# SCH_Media-Remote_2024-07-10.net
KiCad netlist of a schematic drawn in EasyEDA
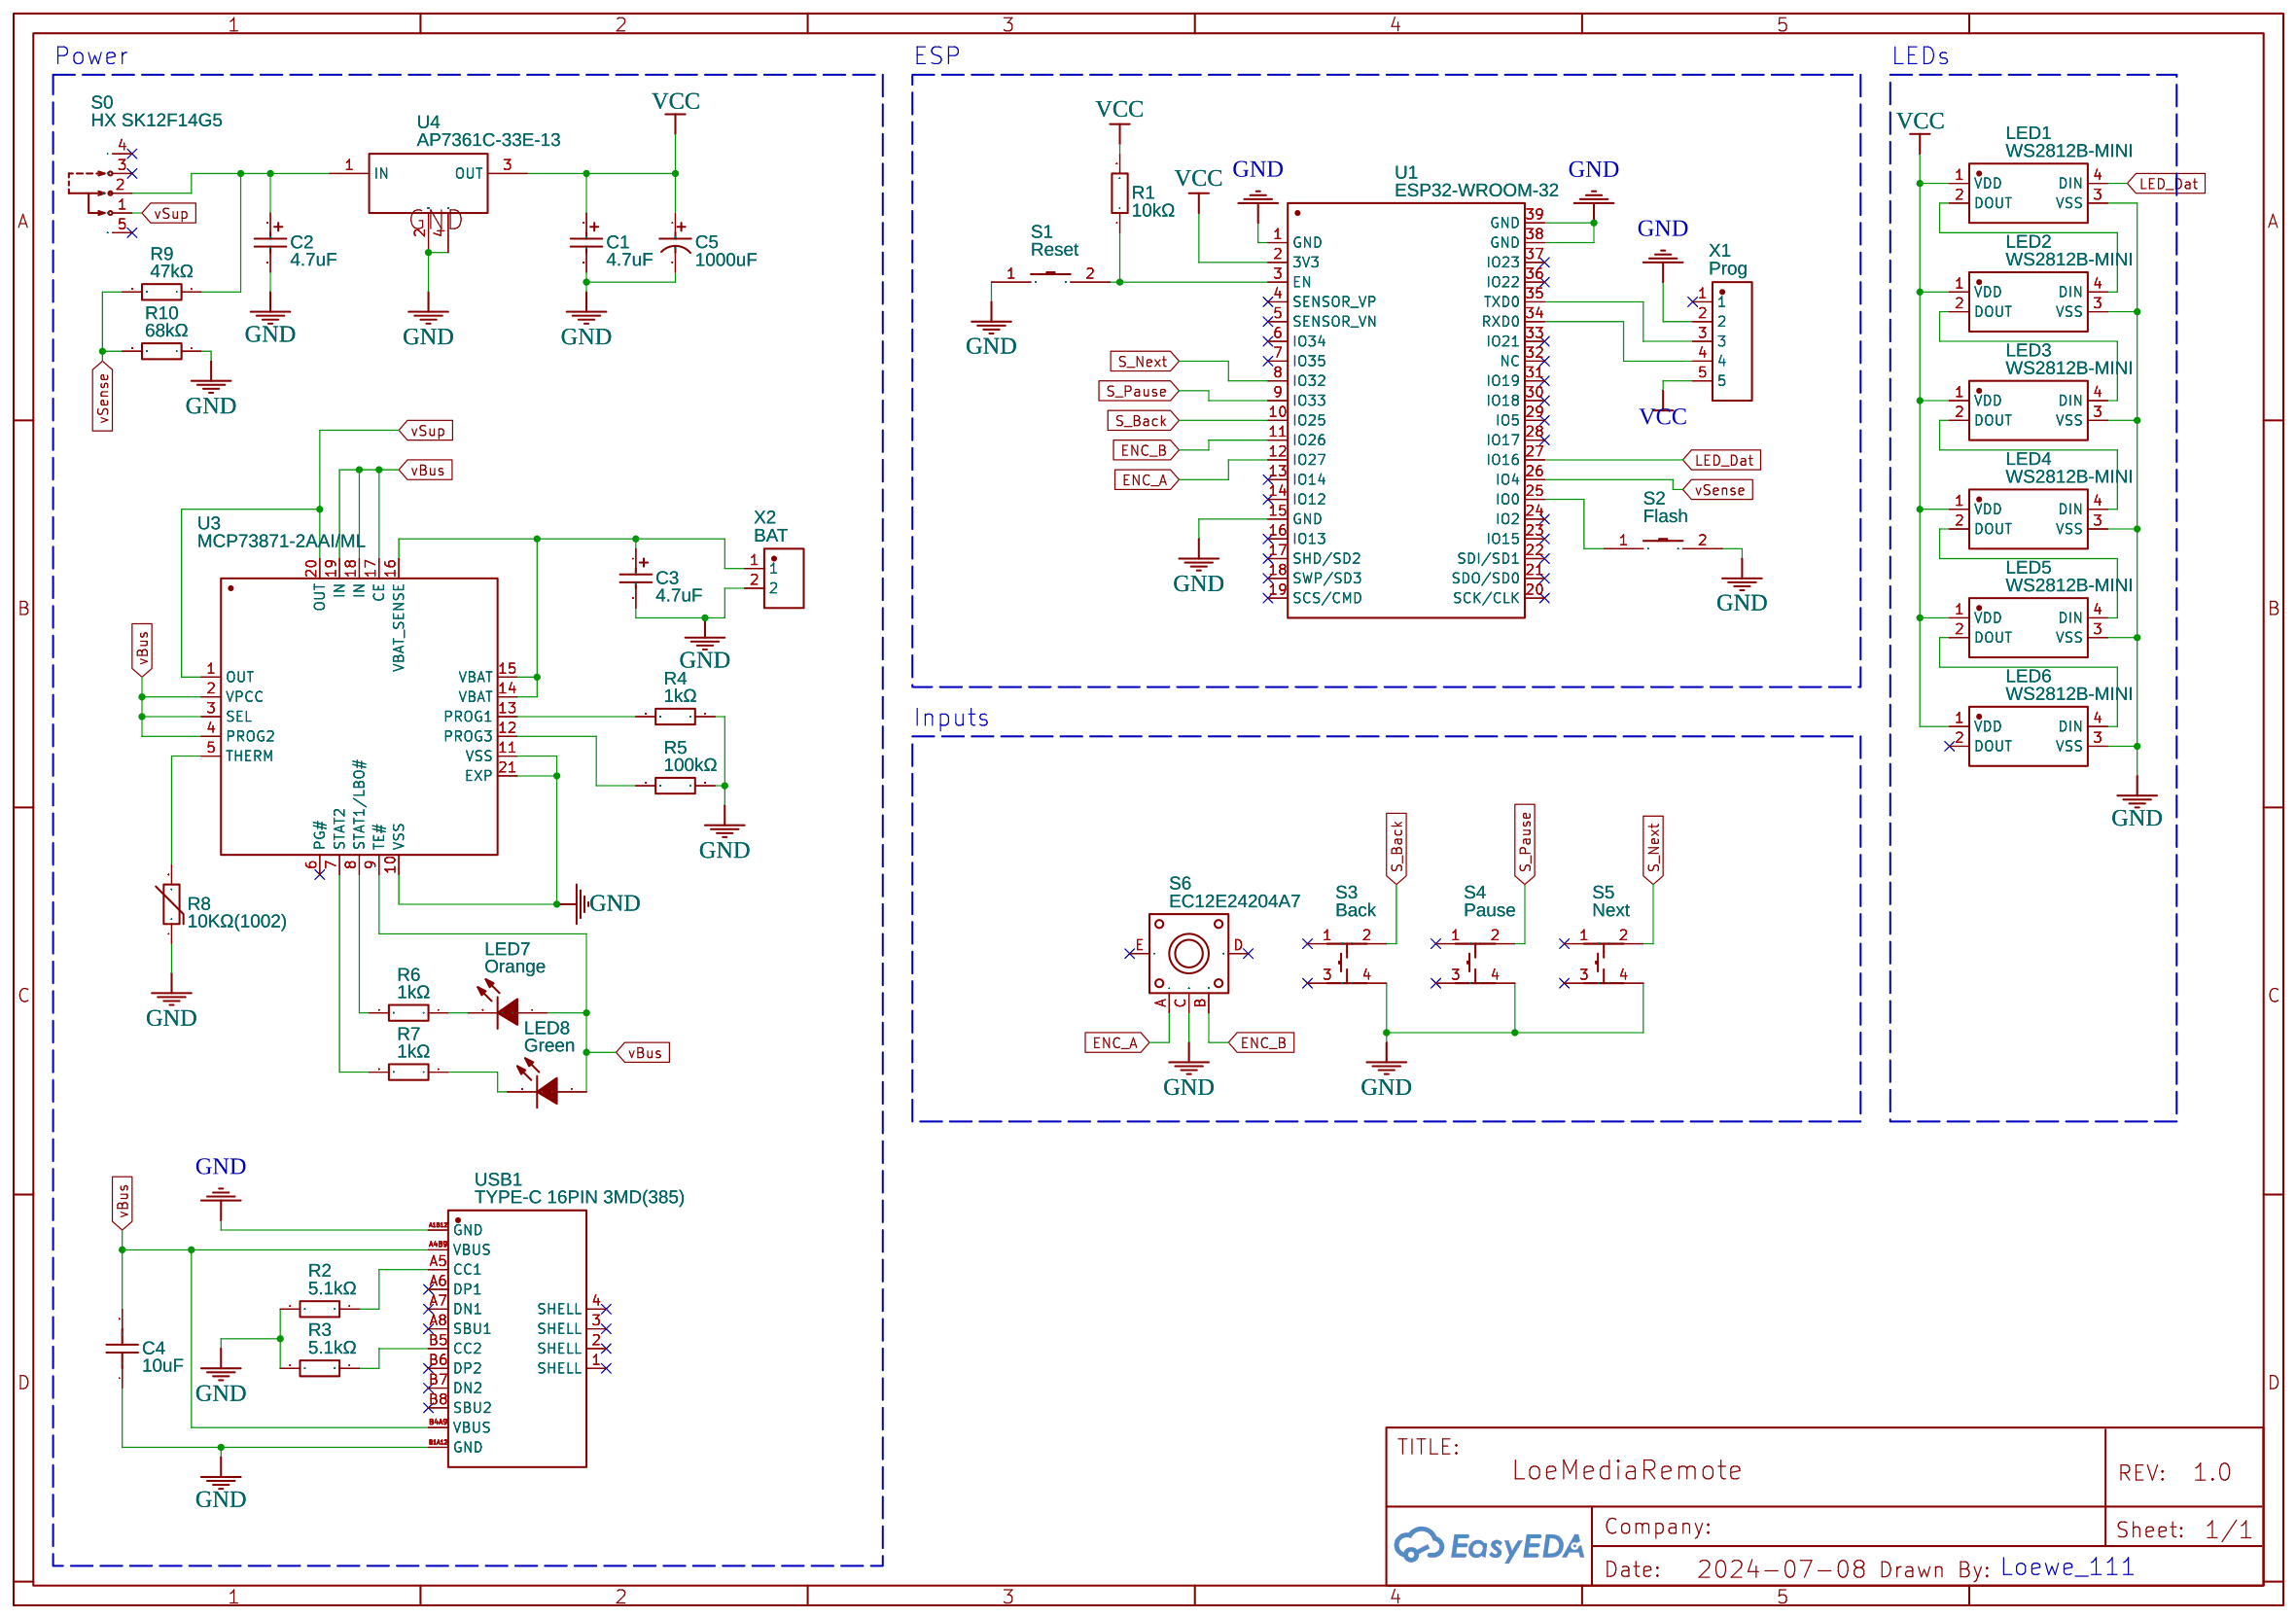
[diagram p0: schematic sheet]

(export (version "E")
  (design (tool "Eeschema 10.0.6"))
  (components
    (comp (ref "C1")
      (value "4.7uF")
      (fields
        (field (name "Manufacturer Part") "CA45-A-16V-4.7uF-K")
        (field (name "Manufacturer") "CEC(振华新云)")
      )
      (libsource (lib "") (part "CA45-A-16V-4.7UF-K"))
    )
    (comp (ref "C2")
      (value "4.7uF")
      (fields
        (field (name "Manufacturer Part") "CA45-A-16V-4.7uF-K")
        (field (name "Manufacturer") "CEC(振华新云)")
      )
      (libsource (lib "") (part "CA45-A-16V-4.7UF-K"))
    )
    (comp (ref "C3")
      (value "4.7uF")
      (fields
        (field (name "Manufacturer Part") "CA45-A-16V-4.7uF-K")
        (field (name "Manufacturer") "CEC(振华新云)")
      )
      (libsource (lib "") (part "CA45-A-16V-4.7UF-K"))
    )
    (comp (ref "C4")
      (value "10uF")
      (fields
        (field (name "Manufacturer Part") "CL10A106MP8NNNC")
        (field (name "Manufacturer") "SAMSUNG(三星)")
      )
      (libsource (lib "") (part "CL10A106MP8NNNC"))
    )
    (comp (ref "C5")
      (value "1000uF")
      (fields (field (name "Manufacturer Part") "RVT1C102M1010") (field (name "Manufacturer") "ROQANG(容强)"))
      (libsource (lib "") (part "RVT1C102M1010"))
    )
    (comp (ref "LED1")
      (value "WS2812B-MINI")
      (fields
        (field (name "Manufacturer Part") "WS2812B-MINI-V3/W")
        (field (name "Manufacturer") "worldsemi")
      )
      (libsource (lib "") (part "WS2812B-MINI"))
    )
    (comp (ref "LED2")
      (value "WS2812B-MINI")
      (fields
        (field (name "Manufacturer Part") "WS2812B-MINI-V3/W")
        (field (name "Manufacturer") "worldsemi")
      )
      (libsource (lib "") (part "WS2812B-MINI"))
    )
    (comp (ref "LED3")
      (value "WS2812B-MINI")
      (fields
        (field (name "Manufacturer Part") "WS2812B-MINI-V3/W")
        (field (name "Manufacturer") "worldsemi")
      )
      (libsource (lib "") (part "WS2812B-MINI"))
    )
    (comp (ref "LED4")
      (value "WS2812B-MINI")
      (fields
        (field (name "Manufacturer Part") "WS2812B-MINI-V3/W")
        (field (name "Manufacturer") "worldsemi")
      )
      (libsource (lib "") (part "WS2812B-MINI"))
    )
    (comp (ref "LED5")
      (value "WS2812B-MINI")
      (fields
        (field (name "Manufacturer Part") "WS2812B-MINI-V3/W")
        (field (name "Manufacturer") "worldsemi")
      )
      (libsource (lib "") (part "WS2812B-MINI"))
    )
    (comp (ref "LED6")
      (value "WS2812B-MINI")
      (fields
        (field (name "Manufacturer Part") "WS2812B-MINI-V3/W")
        (field (name "Manufacturer") "worldsemi")
      )
      (libsource (lib "") (part "WS2812B-MINI"))
    )
    (comp (ref "LED7")
      (value "Orange")
      (fields (field (name "Manufacturer Part") "SZYY0603O") (field (name "Manufacturer") "yongyu(永裕光电)"))
      (libsource (lib "") (part "SZYY0603O"))
    )
    (comp (ref "LED8")
      (value "Green")
      (fields (field (name "Manufacturer Part") "SZYY0603G") (field (name "Manufacturer") "yongyu(永裕光电)"))
      (libsource (lib "") (part "SZYY0603G"))
    )
    (comp (ref "R1")
      (value "10kΩ")
      (fields
        (field (name "Manufacturer Part") "0603WAF1002T5E")
        (field (name "Manufacturer") "UNI-ROYAL(厚声)")
      )
      (libsource (lib "") (part "0603WAF1002T5E"))
    )
    (comp (ref "R2")
      (value "5.1kΩ")
      (fields
        (field (name "Manufacturer Part") "0603WAF5101T5E")
        (field (name "Manufacturer") "UNI-ROYAL(厚声)")
      )
      (libsource (lib "") (part "0603WAF5101T5E"))
    )
    (comp (ref "R3")
      (value "5.1kΩ")
      (fields
        (field (name "Manufacturer Part") "0603WAF5101T5E")
        (field (name "Manufacturer") "UNI-ROYAL(厚声)")
      )
      (libsource (lib "") (part "0603WAF5101T5E"))
    )
    (comp (ref "R4")
      (value "1kΩ")
      (fields (field (name "Manufacturer Part") "RC0603FR-071KL") (field (name "Manufacturer") "YAGEO(国巨)"))
      (libsource (lib "") (part "RC0603FR-071KL"))
    )
    (comp (ref "R5")
      (value "100kΩ")
      (fields (field (name "Manufacturer Part") "RC0603FR-07100KL") (field (name "Manufacturer") "YAGEO(国巨)"))
      (libsource (lib "") (part "RC0603FR-07100KL"))
    )
    (comp (ref "R6")
      (value "1kΩ")
      (fields (field (name "Manufacturer Part") "RC0603FR-071KL") (field (name "Manufacturer") "YAGEO(国巨)"))
      (libsource (lib "") (part "RC0603FR-071KL"))
    )
    (comp (ref "R7")
      (value "1kΩ")
      (fields (field (name "Manufacturer Part") "RC0603FR-071KL") (field (name "Manufacturer") "YAGEO(国巨)"))
      (libsource (lib "") (part "RC0603FR-071KL"))
    )
    (comp (ref "R8")
      (value "10KΩ(1002)")
      (fields (field (name "Manufacturer Part") "NCP18XH103F03RB") (field (name "Manufacturer") "muRata(村田)"))
      (libsource (lib "") (part "NCP18XH103F03RB"))
    )
    (comp (ref "R9")
      (value "47kΩ")
      (fields (field (name "Manufacturer Part") "RC0603FR-0747KL") (field (name "Manufacturer") "YAGEO(国巨)"))
      (libsource (lib "") (part "RC0603FR-0747KL"))
    )
    (comp (ref "R10")
      (value "68kΩ")
      (fields (field (name "Manufacturer Part") "RC0603FR-0768KL") (field (name "Manufacturer") "YAGEO(国巨)"))
      (libsource (lib "") (part "RC0603FR-0768KL"))
    )
    (comp (ref "S0")
      (value "HX SK12F14G5")
      (fields (field (name "Manufacturer") "hanxia(韩下)"))
      (libsource (lib "") (part "HX SK12F14G5"))
    )
    (comp (ref "S1")
      (value "Reset")
      (fields
        (field (name "Manufacturer Part") "TS-1101-C-W")
        (field (name "Manufacturer") "XKB Connectivity(中国星坤)")
      )
      (libsource (lib "") (part "TS-1101-C-W"))
    )
    (comp (ref "S2")
      (value "Flash")
      (fields
        (field (name "Manufacturer Part") "TS-1101-C-W")
        (field (name "Manufacturer") "XKB Connectivity(中国星坤)")
      )
      (libsource (lib "") (part "TS-1101-C-W"))
    )
    (comp (ref "S3")
      (value "Back")
      (fields (field (name "Manufacturer Part") "TS-1094TS-B3D2") (field (name "Manufacturer") "Yuandi(元迪)"))
      (libsource (lib "") (part "TS-1094TS-B3D2"))
    )
    (comp (ref "S4")
      (value "Pause")
      (fields (field (name "Manufacturer Part") "TS-1094TS-B3D2") (field (name "Manufacturer") "Yuandi(元迪)"))
      (libsource (lib "") (part "TS-1094TS-B3D2"))
    )
    (comp (ref "S5")
      (value "Next")
      (fields (field (name "Manufacturer Part") "TS-1094TS-B3D2") (field (name "Manufacturer") "Yuandi(元迪)"))
      (libsource (lib "") (part "TS-1094TS-B3D2"))
    )
    (comp (ref "S6")
      (value "EC12E24204A7")
      (fields (field (name "Manufacturer") "ALPSALPINE(阿尔卑斯阿尔派)"))
      (libsource (lib "") (part "EC12E24204A7"))
    )
    (comp (ref "U1")
      (value "ESP32-WROOM-32")
      (fields
        (field (name "Manufacturer Part") "ESP32-WROOM-32-N4")
        (field (name "Manufacturer") "ESPRESSIF(乐鑫)")
      )
      (libsource (lib "") (part "ESP32-WROOM-32"))
    )
    (comp (ref "U3")
      (value "MCP73871-2AAI/ML")
      (fields (field (name "Manufacturer") "MICROCHIP(美国微芯)"))
      (libsource (lib "") (part "MCP73871-2AAI/ML"))
    )
    (comp (ref "U4")
      (value "AP7361C-33E-13")
      (fields (field (name "Manufacturer") "Diodes Incorporated"))
      (libsource (lib "") (part "AP7361C-33E-13"))
    )
    (comp (ref "USB1")
      (value "TYPE-C 16PIN 3MD(385)")
      (fields (field (name "Manufacturer") "SHOU HAN(首韩)"))
      (libsource (lib "") (part "TYPE-C 16PIN 3MD(385)"))
    )
    (comp (ref "X1")
      (value "Prog")
      (fields
        (field (name "Manufacturer Part") "X6511WVS-05H-C60D48R1")
        (field (name "Manufacturer") "XKB Connection(中国星坤)")
      )
      (libsource (lib "") (part "X6511WVS-05H-C60D48R1"))
    )
    (comp (ref "X2")
      (value "BAT")
      (fields
        (field (name "Manufacturer Part") "ZX-XH2.54-2PZZ")
        (field (name "Manufacturer") "Megastar(兆星)")
      )
      (libsource (lib "") (part "ZX-XH2.54-2PZZ"))
    )
  )
  (nets
    (net (code "1") (name "ENC_A") (class "Default")
      (node (ref "S6") (pin "A") (pinfunction "A_A") (pintype "unspecified"))
      (node (ref "U1") (pin "12") (pinfunction "IO27_12") (pintype "unspecified"))
    )
    (net (code "2") (name "ENC_B") (class "Default")
      (node (ref "S6") (pin "B") (pinfunction "B_B") (pintype "unspecified"))
      (node (ref "U1") (pin "11") (pinfunction "IO26_11") (pintype "unspecified"))
    )
    (net (code "3") (name "GND") (class "Default")
      (node (ref "C1") (pin "2") (pinfunction "2_2") (pintype "input"))
      (node (ref "C2") (pin "2") (pinfunction "2_2") (pintype "input"))
      (node (ref "C3") (pin "2") (pinfunction "2_2") (pintype "input"))
      (node (ref "C4") (pin "1") (pinfunction "1_1") (pintype "unspecified"))
      (node (ref "C5") (pin "2") (pinfunction "2_2") (pintype "input"))
      (node (ref "LED1") (pin "3") (pinfunction "VSS_3") (pintype "unspecified"))
      (node (ref "LED2") (pin "3") (pinfunction "VSS_3") (pintype "unspecified"))
      (node (ref "LED3") (pin "3") (pinfunction "VSS_3") (pintype "unspecified"))
      (node (ref "LED4") (pin "3") (pinfunction "VSS_3") (pintype "unspecified"))
      (node (ref "LED5") (pin "3") (pinfunction "VSS_3") (pintype "unspecified"))
      (node (ref "LED6") (pin "3") (pinfunction "VSS_3") (pintype "unspecified"))
      (node (ref "R10") (pin "1") (pinfunction "1_1") (pintype "input"))
      (node (ref "R2") (pin "2") (pinfunction "2_2") (pintype "input"))
      (node (ref "R3") (pin "2") (pinfunction "2_2") (pintype "input"))
      (node (ref "R4") (pin "1") (pinfunction "1_1") (pintype "input"))
      (node (ref "R5") (pin "1") (pinfunction "1_1") (pintype "unspecified"))
      (node (ref "R8") (pin "1") (pinfunction "1_1") (pintype "input"))
      (node (ref "S1") (pin "1") (pinfunction "1_1") (pintype "unspecified"))
      (node (ref "S2") (pin "2") (pinfunction "2_2") (pintype "unspecified"))
      (node (ref "S3") (pin "4") (pinfunction "4_4") (pintype "unspecified"))
      (node (ref "S4") (pin "4") (pinfunction "4_4") (pintype "unspecified"))
      (node (ref "S5") (pin "4") (pinfunction "4_4") (pintype "unspecified"))
      (node (ref "S6") (pin "C") (pinfunction "C_C") (pintype "unspecified"))
      (node (ref "U1") (pin "1") (pinfunction "GND_1") (pintype "unspecified"))
      (node (ref "U1") (pin "15") (pinfunction "GND_15") (pintype "unspecified"))
      (node (ref "U1") (pin "38") (pinfunction "GND_38") (pintype "unspecified"))
      (node (ref "U1") (pin "39") (pinfunction "GND_39") (pintype "unspecified"))
      (node (ref "U3") (pin "10") (pinfunction "VSS_10") (pintype "unspecified"))
      (node (ref "U3") (pin "11") (pinfunction "VSS_11") (pintype "unspecified"))
      (node (ref "U3") (pin "21") (pinfunction "EXP_21") (pintype "unspecified"))
      (node (ref "U4") (pin "2") (pinfunction "GND_2") (pintype "passive"))
      (node (ref "U4") (pin "4") (pinfunction "GND_4") (pintype "passive"))
      (node (ref "USB1") (pin "A1B12") (pinfunction "GND_A1B12") (pintype "unspecified"))
      (node (ref "USB1") (pin "B1A12") (pinfunction "GND_B1A12") (pintype "unspecified"))
      (node (ref "X1") (pin "2") (pinfunction "2_2") (pintype "unspecified"))
      (node (ref "X2") (pin "2") (pinfunction "2_2") (pintype "unspecified"))
    )
    (net (code "4") (name "LED_Dat") (class "Default")
      (node (ref "LED1") (pin "4") (pinfunction "DIN_4") (pintype "unspecified"))
      (node (ref "U1") (pin "27") (pinfunction "IO16_27") (pintype "unspecified"))
    )
    (net (code "5") (name "Net-(LED1-DOUT)") (class "Default")
      (node (ref "LED1") (pin "2") (pinfunction "DOUT_2") (pintype "unspecified"))
      (node (ref "LED2") (pin "4") (pinfunction "DIN_4") (pintype "unspecified"))
    )
    (net (code "6") (name "Net-(LED2-DOUT)") (class "Default")
      (node (ref "LED2") (pin "2") (pinfunction "DOUT_2") (pintype "unspecified"))
      (node (ref "LED3") (pin "4") (pinfunction "DIN_4") (pintype "unspecified"))
    )
    (net (code "7") (name "Net-(LED3-DOUT)") (class "Default")
      (node (ref "LED3") (pin "2") (pinfunction "DOUT_2") (pintype "unspecified"))
      (node (ref "LED4") (pin "4") (pinfunction "DIN_4") (pintype "unspecified"))
    )
    (net (code "8") (name "Net-(LED4-DOUT)") (class "Default")
      (node (ref "LED4") (pin "2") (pinfunction "DOUT_2") (pintype "unspecified"))
      (node (ref "LED5") (pin "4") (pinfunction "DIN_4") (pintype "unspecified"))
    )
    (net (code "9") (name "Net-(LED5-DOUT)") (class "Default")
      (node (ref "LED5") (pin "2") (pinfunction "DOUT_2") (pintype "unspecified"))
      (node (ref "LED6") (pin "4") (pinfunction "DIN_4") (pintype "unspecified"))
    )
    (net (code "10") (name "Net-(LED7--)") (class "Default")
      (node (ref "LED7") (pin "2") (pinfunction "-_2") (pintype "unspecified"))
      (node (ref "R6") (pin "1") (pinfunction "1_1") (pintype "input"))
    )
    (net (code "11") (name "Net-(LED8--)") (class "Default")
      (node (ref "LED8") (pin "2") (pinfunction "-_2") (pintype "unspecified"))
      (node (ref "R7") (pin "1") (pinfunction "1_1") (pintype "input"))
    )
    (net (code "12") (name "Net-(U1-EN)") (class "Default")
      (node (ref "R1") (pin "1") (pinfunction "1_1") (pintype "input"))
      (node (ref "S1") (pin "2") (pinfunction "2_2") (pintype "unspecified"))
      (node (ref "U1") (pin "3") (pinfunction "EN_3") (pintype "unspecified"))
    )
    (net (code "13") (name "Net-(U1-IO0)") (class "Default")
      (node (ref "S2") (pin "1") (pinfunction "1_1") (pintype "unspecified"))
      (node (ref "U1") (pin "25") (pinfunction "IO0_25") (pintype "unspecified"))
    )
    (net (code "14") (name "Net-(U1-RXD0)") (class "Default")
      (node (ref "U1") (pin "34") (pinfunction "RXD0_34") (pintype "unspecified"))
      (node (ref "X1") (pin "4") (pinfunction "4_4") (pintype "unspecified"))
    )
    (net (code "15") (name "Net-(U1-TXD0)") (class "Default")
      (node (ref "U1") (pin "35") (pinfunction "TXD0_35") (pintype "unspecified"))
      (node (ref "X1") (pin "3") (pinfunction "3_3") (pintype "unspecified"))
    )
    (net (code "16") (name "Net-(U3-PROG1)") (class "Default")
      (node (ref "R4") (pin "2") (pinfunction "2_2") (pintype "input"))
      (node (ref "U3") (pin "13") (pinfunction "PROG1_13") (pintype "unspecified"))
    )
    (net (code "17") (name "Net-(U3-PROG3)") (class "Default")
      (node (ref "R5") (pin "2") (pinfunction "2_2") (pintype "unspecified"))
      (node (ref "U3") (pin "12") (pinfunction "PROG3_12") (pintype "unspecified"))
    )
    (net (code "18") (name "Net-(U3-STAT1{slash}LBO#)") (class "Default")
      (node (ref "R6") (pin "2") (pinfunction "2_2") (pintype "input"))
      (node (ref "U3") (pin "8") (pinfunction "STAT1/LBO#_8") (pintype "unspecified"))
    )
    (net (code "19") (name "Net-(U3-STAT2)") (class "Default")
      (node (ref "R7") (pin "2") (pinfunction "2_2") (pintype "input"))
      (node (ref "U3") (pin "7") (pinfunction "STAT2_7") (pintype "unspecified"))
    )
    (net (code "20") (name "Net-(U3-THERM)") (class "Default")
      (node (ref "R8") (pin "2") (pinfunction "2_2") (pintype "input"))
      (node (ref "U3") (pin "5") (pinfunction "THERM_5") (pintype "unspecified"))
    )
    (net (code "21") (name "Net-(U3-VBAT_SENSE)") (class "Default")
      (node (ref "C3") (pin "1") (pinfunction "1_1") (pintype "input"))
      (node (ref "U3") (pin "14") (pinfunction "VBAT_14") (pintype "unspecified"))
      (node (ref "U3") (pin "15") (pinfunction "VBAT_15") (pintype "unspecified"))
      (node (ref "U3") (pin "16") (pinfunction "VBAT_SENSE_16") (pintype "unspecified"))
      (node (ref "X2") (pin "1") (pinfunction "1_1") (pintype "unspecified"))
    )
    (net (code "22") (name "Net-(U4-IN)") (class "Default")
      (node (ref "C2") (pin "1") (pinfunction "1_1") (pintype "input"))
      (node (ref "R9") (pin "1") (pinfunction "1_1") (pintype "input"))
      (node (ref "S0") (pin "2") (pinfunction "2_2") (pintype "unspecified"))
      (node (ref "U4") (pin "1") (pinfunction "IN_1") (pintype "passive"))
    )
    (net (code "23") (name "Net-(USB1-CC1)") (class "Default")
      (node (ref "R2") (pin "1") (pinfunction "1_1") (pintype "input"))
      (node (ref "USB1") (pin "A5") (pinfunction "CC1_A5") (pintype "unspecified"))
    )
    (net (code "24") (name "Net-(USB1-CC2)") (class "Default")
      (node (ref "R3") (pin "1") (pinfunction "1_1") (pintype "input"))
      (node (ref "USB1") (pin "B5") (pinfunction "CC2_B5") (pintype "unspecified"))
    )
    (net (code "25") (name "S_Back") (class "Default")
      (node (ref "S3") (pin "2") (pinfunction "2_2") (pintype "unspecified"))
      (node (ref "U1") (pin "10") (pinfunction "IO25_10") (pintype "unspecified"))
    )
    (net (code "26") (name "S_Next") (class "Default")
      (node (ref "S5") (pin "2") (pinfunction "2_2") (pintype "unspecified"))
      (node (ref "U1") (pin "8") (pinfunction "IO32_8") (pintype "unspecified"))
    )
    (net (code "27") (name "S_Pause") (class "Default")
      (node (ref "S4") (pin "2") (pinfunction "2_2") (pintype "unspecified"))
      (node (ref "U1") (pin "9") (pinfunction "IO33_9") (pintype "unspecified"))
    )
    (net (code "28") (name "VCC") (class "Default")
      (node (ref "C1") (pin "1") (pinfunction "1_1") (pintype "input"))
      (node (ref "C5") (pin "1") (pinfunction "1_1") (pintype "input"))
      (node (ref "LED1") (pin "1") (pinfunction "VDD_1") (pintype "unspecified"))
      (node (ref "LED2") (pin "1") (pinfunction "VDD_1") (pintype "unspecified"))
      (node (ref "LED3") (pin "1") (pinfunction "VDD_1") (pintype "unspecified"))
      (node (ref "LED4") (pin "1") (pinfunction "VDD_1") (pintype "unspecified"))
      (node (ref "LED5") (pin "1") (pinfunction "VDD_1") (pintype "unspecified"))
      (node (ref "LED6") (pin "1") (pinfunction "VDD_1") (pintype "unspecified"))
      (node (ref "R1") (pin "2") (pinfunction "2_2") (pintype "input"))
      (node (ref "U1") (pin "2") (pinfunction "3V3_2") (pintype "unspecified"))
      (node (ref "U4") (pin "3") (pinfunction "OUT_3") (pintype "passive"))
      (node (ref "X1") (pin "5") (pinfunction "5_5") (pintype "unspecified"))
    )
    (net (code "29") (name "unconnected-(LED6-DOUT-Pad2)") (class "Default")
      (node (ref "LED6") (pin "2") (pinfunction "DOUT_2") (pintype "unspecified+no_connect"))
    )
    (net (code "30") (name "unconnected-(S0-Pad3)") (class "Default")
      (node (ref "S0") (pin "3") (pinfunction "3_3") (pintype "unspecified+no_connect"))
    )
    (net (code "31") (name "unconnected-(S0-Pad4)") (class "Default")
      (node (ref "S0") (pin "4") (pinfunction "4_4") (pintype "unspecified+no_connect"))
    )
    (net (code "32") (name "unconnected-(S0-Pad5)") (class "Default")
      (node (ref "S0") (pin "5") (pinfunction "5_5") (pintype "unspecified+no_connect"))
    )
    (net (code "33") (name "unconnected-(S3-Pad1)") (class "Default")
      (node (ref "S3") (pin "1") (pinfunction "1_1") (pintype "unspecified+no_connect"))
    )
    (net (code "34") (name "unconnected-(S3-Pad3)") (class "Default")
      (node (ref "S3") (pin "3") (pinfunction "3_3") (pintype "unspecified+no_connect"))
    )
    (net (code "35") (name "unconnected-(S4-Pad1)") (class "Default")
      (node (ref "S4") (pin "1") (pinfunction "1_1") (pintype "unspecified+no_connect"))
    )
    (net (code "36") (name "unconnected-(S4-Pad3)") (class "Default")
      (node (ref "S4") (pin "3") (pinfunction "3_3") (pintype "unspecified+no_connect"))
    )
    (net (code "37") (name "unconnected-(S5-Pad1)") (class "Default")
      (node (ref "S5") (pin "1") (pinfunction "1_1") (pintype "unspecified+no_connect"))
    )
    (net (code "38") (name "unconnected-(S5-Pad3)") (class "Default")
      (node (ref "S5") (pin "3") (pinfunction "3_3") (pintype "unspecified+no_connect"))
    )
    (net (code "39") (name "unconnected-(S6-PadD)") (class "Default")
      (node (ref "S6") (pin "D") (pinfunction "D_D") (pintype "unspecified+no_connect"))
    )
    (net (code "40") (name "unconnected-(S6-PadE)") (class "Default")
      (node (ref "S6") (pin "E") (pinfunction "E_E") (pintype "unspecified+no_connect"))
    )
    (net (code "41") (name "unconnected-(U1-IO2-Pad24)") (class "Default")
      (node (ref "U1") (pin "24") (pinfunction "IO2_24") (pintype "unspecified+no_connect"))
    )
    (net (code "42") (name "unconnected-(U1-IO5-Pad29)") (class "Default")
      (node (ref "U1") (pin "29") (pinfunction "IO5_29") (pintype "unspecified+no_connect"))
    )
    (net (code "43") (name "unconnected-(U1-IO12-Pad14)") (class "Default")
      (node (ref "U1") (pin "14") (pinfunction "IO12_14") (pintype "unspecified+no_connect"))
    )
    (net (code "44") (name "unconnected-(U1-IO13-Pad16)") (class "Default")
      (node (ref "U1") (pin "16") (pinfunction "IO13_16") (pintype "unspecified+no_connect"))
    )
    (net (code "45") (name "unconnected-(U1-IO14-Pad13)") (class "Default")
      (node (ref "U1") (pin "13") (pinfunction "IO14_13") (pintype "unspecified+no_connect"))
    )
    (net (code "46") (name "unconnected-(U1-IO15-Pad23)") (class "Default")
      (node (ref "U1") (pin "23") (pinfunction "IO15_23") (pintype "unspecified+no_connect"))
    )
    (net (code "47") (name "unconnected-(U1-IO17-Pad28)") (class "Default")
      (node (ref "U1") (pin "28") (pinfunction "IO17_28") (pintype "unspecified+no_connect"))
    )
    (net (code "48") (name "unconnected-(U1-IO18-Pad30)") (class "Default")
      (node (ref "U1") (pin "30") (pinfunction "IO18_30") (pintype "unspecified+no_connect"))
    )
    (net (code "49") (name "unconnected-(U1-IO19-Pad31)") (class "Default")
      (node (ref "U1") (pin "31") (pinfunction "IO19_31") (pintype "unspecified+no_connect"))
    )
    (net (code "50") (name "unconnected-(U1-IO21-Pad33)") (class "Default")
      (node (ref "U1") (pin "33") (pinfunction "IO21_33") (pintype "unspecified+no_connect"))
    )
    (net (code "51") (name "unconnected-(U1-IO22-Pad36)") (class "Default")
      (node (ref "U1") (pin "36") (pinfunction "IO22_36") (pintype "unspecified+no_connect"))
    )
    (net (code "52") (name "unconnected-(U1-IO23-Pad37)") (class "Default")
      (node (ref "U1") (pin "37") (pinfunction "IO23_37") (pintype "unspecified+no_connect"))
    )
    (net (code "53") (name "unconnected-(U1-IO34-Pad6)") (class "Default")
      (node (ref "U1") (pin "6") (pinfunction "IO34_6") (pintype "unspecified+no_connect"))
    )
    (net (code "54") (name "unconnected-(U1-IO35-Pad7)") (class "Default")
      (node (ref "U1") (pin "7") (pinfunction "IO35_7") (pintype "unspecified+no_connect"))
    )
    (net (code "55") (name "unconnected-(U1-NC-Pad32)") (class "Default")
      (node (ref "U1") (pin "32") (pinfunction "NC_32") (pintype "unspecified+no_connect"))
    )
    (net (code "56") (name "unconnected-(U1-SCK{slash}CLK-Pad20)") (class "Default")
      (node (ref "U1") (pin "20") (pinfunction "SCK/CLK_20") (pintype "unspecified+no_connect"))
    )
    (net (code "57") (name "unconnected-(U1-SCS{slash}CMD-Pad19)") (class "Default")
      (node (ref "U1") (pin "19") (pinfunction "SCS/CMD_19") (pintype "unspecified+no_connect"))
    )
    (net (code "58") (name "unconnected-(U1-SDI{slash}SD1-Pad22)") (class "Default")
      (node (ref "U1") (pin "22") (pinfunction "SDI/SD1_22") (pintype "unspecified+no_connect"))
    )
    (net (code "59") (name "unconnected-(U1-SDO{slash}SD0-Pad21)") (class "Default")
      (node (ref "U1") (pin "21") (pinfunction "SDO/SD0_21") (pintype "unspecified+no_connect"))
    )
    (net (code "60") (name "unconnected-(U1-SENSOR_VN-Pad5)") (class "Default")
      (node (ref "U1") (pin "5") (pinfunction "SENSOR_VN_5") (pintype "unspecified+no_connect"))
    )
    (net (code "61") (name "unconnected-(U1-SENSOR_VP-Pad4)") (class "Default")
      (node (ref "U1") (pin "4") (pinfunction "SENSOR_VP_4") (pintype "unspecified+no_connect"))
    )
    (net (code "62") (name "unconnected-(U1-SHD{slash}SD2-Pad17)") (class "Default")
      (node (ref "U1") (pin "17") (pinfunction "SHD/SD2_17") (pintype "unspecified+no_connect"))
    )
    (net (code "63") (name "unconnected-(U1-SWP{slash}SD3-Pad18)") (class "Default")
      (node (ref "U1") (pin "18") (pinfunction "SWP/SD3_18") (pintype "unspecified+no_connect"))
    )
    (net (code "64") (name "unconnected-(U3-PG#-Pad6)") (class "Default")
      (node (ref "U3") (pin "6") (pinfunction "PG#_6") (pintype "unspecified+no_connect"))
    )
    (net (code "65") (name "unconnected-(USB1-DN1-PadA7)") (class "Default")
      (node (ref "USB1") (pin "A7") (pinfunction "DN1_A7") (pintype "unspecified+no_connect"))
    )
    (net (code "66") (name "unconnected-(USB1-DN2-PadB7)") (class "Default")
      (node (ref "USB1") (pin "B7") (pinfunction "DN2_B7") (pintype "unspecified+no_connect"))
    )
    (net (code "67") (name "unconnected-(USB1-DP1-PadA6)") (class "Default")
      (node (ref "USB1") (pin "A6") (pinfunction "DP1_A6") (pintype "unspecified+no_connect"))
    )
    (net (code "68") (name "unconnected-(USB1-DP2-PadB6)") (class "Default")
      (node (ref "USB1") (pin "B6") (pinfunction "DP2_B6") (pintype "unspecified+no_connect"))
    )
    (net (code "69") (name "unconnected-(USB1-SBU1-PadA8)") (class "Default")
      (node (ref "USB1") (pin "A8") (pinfunction "SBU1_A8") (pintype "unspecified+no_connect"))
    )
    (net (code "70") (name "unconnected-(USB1-SBU2-PadB8)") (class "Default")
      (node (ref "USB1") (pin "B8") (pinfunction "SBU2_B8") (pintype "unspecified+no_connect"))
    )
    (net (code "71") (name "unconnected-(USB1-SHELL-Pad1)") (class "Default")
      (node (ref "USB1") (pin "1") (pinfunction "SHELL_1") (pintype "unspecified+no_connect"))
    )
    (net (code "72") (name "unconnected-(USB1-SHELL-Pad2)") (class "Default")
      (node (ref "USB1") (pin "2") (pinfunction "SHELL_2") (pintype "unspecified+no_connect"))
    )
    (net (code "73") (name "unconnected-(USB1-SHELL-Pad3)") (class "Default")
      (node (ref "USB1") (pin "3") (pinfunction "SHELL_3") (pintype "unspecified+no_connect"))
    )
    (net (code "74") (name "unconnected-(USB1-SHELL-Pad4)") (class "Default")
      (node (ref "USB1") (pin "4") (pinfunction "SHELL_4") (pintype "unspecified+no_connect"))
    )
    (net (code "75") (name "unconnected-(X1-Pad1)") (class "Default")
      (node (ref "X1") (pin "1") (pinfunction "1_1") (pintype "unspecified+no_connect"))
    )
    (net (code "76") (name "vBus") (class "Default")
      (node (ref "C4") (pin "2") (pinfunction "2_2") (pintype "unspecified"))
      (node (ref "LED7") (pin "1") (pinfunction "+_1") (pintype "unspecified"))
      (node (ref "LED8") (pin "1") (pinfunction "+_1") (pintype "unspecified"))
      (node (ref "U3") (pin "17") (pinfunction "CE_17") (pintype "unspecified"))
      (node (ref "U3") (pin "18") (pinfunction "IN_18") (pintype "unspecified"))
      (node (ref "U3") (pin "19") (pinfunction "IN_19") (pintype "unspecified"))
      (node (ref "U3") (pin "2") (pinfunction "VPCC_2") (pintype "unspecified"))
      (node (ref "U3") (pin "3") (pinfunction "SEL_3") (pintype "unspecified"))
      (node (ref "U3") (pin "4") (pinfunction "PROG2_4") (pintype "unspecified"))
      (node (ref "U3") (pin "9") (pinfunction "TE#_9") (pintype "unspecified"))
      (node (ref "USB1") (pin "A4B9") (pinfunction "VBUS_A4B9") (pintype "unspecified"))
      (node (ref "USB1") (pin "B4A9") (pinfunction "VBUS_B4A9") (pintype "unspecified"))
    )
    (net (code "77") (name "vSense") (class "Default")
      (node (ref "R10") (pin "2") (pinfunction "2_2") (pintype "input"))
      (node (ref "R9") (pin "2") (pinfunction "2_2") (pintype "input"))
      (node (ref "U1") (pin "26") (pinfunction "IO4_26") (pintype "unspecified"))
    )
    (net (code "78") (name "vSup") (class "Default")
      (node (ref "S0") (pin "1") (pinfunction "1_1") (pintype "unspecified"))
      (node (ref "U3") (pin "1") (pinfunction "OUT_1") (pintype "unspecified"))
      (node (ref "U3") (pin "20") (pinfunction "OUT_20") (pintype "unspecified"))
    )
  )
)
